# Sheet1.net
KiCad netlist of a schematic drawn in Altium Designer
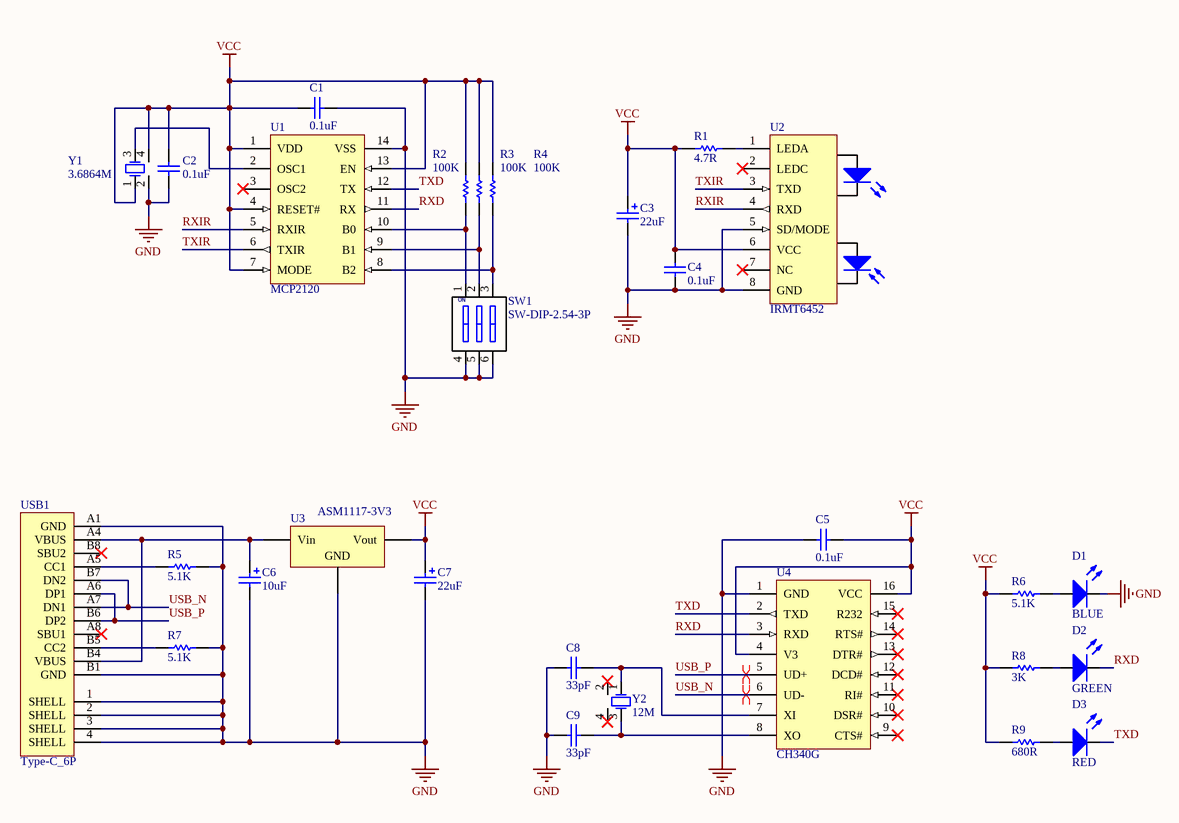
[diagram p0: Sheet1.SchDoc]

(export (version "E")
  (design (tool "Eeschema 10.0.6"))
  (components
    (comp (ref "C1")
      (value "0.1uF")
      (footprint "0603-CAP")
      (libsource (lib "izilzty_Library_Passive") (part "CAP-0603"))
    )
    (comp (ref "C2")
      (value "0.1uF")
      (footprint "0603-CAP")
      (libsource (lib "izilzty_Library_Passive") (part "CAP-0603"))
    )
    (comp (ref "C3")
      (value "22uF")
      (footprint "3216-TCAP_M")
      (libsource (lib "izilzty_Library_Passive") (part "CAP-T-3216"))
    )
    (comp (ref "C4")
      (value "0.1uF")
      (footprint "0603-CAP")
      (libsource (lib "izilzty_Library_Passive") (part "CAP-0603"))
    )
    (comp (ref "C5")
      (value "0.1uF")
      (footprint "0603-CAP")
      (libsource (lib "izilzty_Library_Passive") (part "CAP-0603"))
    )
    (comp (ref "C6")
      (value "10uF")
      (footprint "3216-TCAP_M")
      (libsource (lib "izilzty_Library_Passive") (part "CAP-T-3216"))
    )
    (comp (ref "C7")
      (value "22uF")
      (footprint "3216-TCAP_M")
      (libsource (lib "izilzty_Library_Passive") (part "CAP-T-3216"))
    )
    (comp (ref "C8")
      (value "33pF")
      (footprint "0603-CAP")
      (libsource (lib "izilzty_Library_Passive") (part "CAP-0603"))
    )
    (comp (ref "C9")
      (value "33pF")
      (footprint "0603-CAP")
      (libsource (lib "izilzty_Library_Passive") (part "CAP-0603"))
    )
    (comp (ref "D1")
      (value "BLUE")
      (footprint "0603-LED")
      (libsource (lib "izilzty_Library_Passive") (part "LED-0603"))
    )
    (comp (ref "D2")
      (value "GREEN")
      (footprint "0603-LED")
      (libsource (lib "izilzty_Library_Passive") (part "LED-0603"))
    )
    (comp (ref "D3")
      (value "RED")
      (footprint "0603-LED")
      (libsource (lib "izilzty_Library_Passive") (part "LED-0603"))
    )
    (comp (ref "R1")
      (value "4.7R")
      (footprint "0603-RES")
      (libsource (lib "izilzty_Library_Passive") (part "RES-0603"))
    )
    (comp (ref "R2")
      (value "100K")
      (footprint "0603-RES")
      (libsource (lib "izilzty_Library_Passive") (part "RES-0603"))
    )
    (comp (ref "R3")
      (value "100K")
      (footprint "0603-RES")
      (libsource (lib "izilzty_Library_Passive") (part "RES-0603"))
    )
    (comp (ref "R4")
      (value "100K")
      (footprint "0603-RES")
      (libsource (lib "izilzty_Library_Passive") (part "RES-0603"))
    )
    (comp (ref "R5")
      (value "5.1K")
      (footprint "0603-RES")
      (libsource (lib "izilzty_Library_Passive") (part "RES-0603"))
    )
    (comp (ref "R6")
      (value "5.1K")
      (footprint "0603-RES")
      (libsource (lib "izilzty_Library_Passive") (part "RES-0603"))
    )
    (comp (ref "R7")
      (value "5.1K")
      (footprint "0603-RES")
      (libsource (lib "izilzty_Library_Passive") (part "RES-0603"))
    )
    (comp (ref "R8")
      (value "3K")
      (footprint "0603-RES")
      (libsource (lib "izilzty_Library_Passive") (part "RES-0603"))
    )
    (comp (ref "R9")
      (value "680R")
      (footprint "0603-RES")
      (libsource (lib "izilzty_Library_Passive") (part "RES-0603"))
    )
    (comp (ref "SW1")
      (value "SW-DIP-2.54-3P")
      (footprint "SWITCH-DIP-2.54-3P")
      (libsource (lib "izilzty_Library_Passive") (part "SW-DIP-2.54-3P"))
    )
    (comp (ref "U1")
      (value "MCP2120")
      (footprint "SOP-14_M")
      (description "Infrared Encoder/Decoder")
      (libsource (lib "izilzty_Library_IC") (part "MCP2120"))
    )
    (comp (ref "U2")
      (value "IRMT6452")
      (footprint "IRMT6452_M")
      (description "4 Mb/s Infrared Data Transceiver")
      (libsource (lib "izilzty_Library_IC") (part "IRMT6452"))
    )
    (comp (ref "U3")
      (value "ASM1117-3V3")
      (footprint "SOT-89-3_M")
      (description "Voltage Regular (SOT-89)")
      (libsource (lib "izilzty_Library_IC") (part "VREG-SOT-89"))
    )
    (comp (ref "U4")
      (value "CH340G")
      (footprint "SOP-16_M")
      (description "USB转串口芯片")
      (libsource (lib "izilzty_Library_IC") (part "CH340G"))
    )
    (comp (ref "USB1")
      (value "Type-C_6P")
      (footprint "TYPE-C_16P")
      (libsource (lib "izilzty_Library_Connector") (part "Type-C_6P"))
    )
    (comp (ref "Y1")
      (value "3.6864M")
      (footprint "CRYSTAL_3225SMD_M")
      (description "oscillator")
      (libsource (lib "izilzty_Library_Passive") (part "XTAL-3225SMD"))
    )
    (comp (ref "Y2")
      (value "12M")
      (footprint "CRYSTAL_3225SMD_M")
      (description "crystal")
      (libsource (lib "izilzty_Library_Passive") (part "XTAL-3225SMD"))
    )
  )
  (nets
    (net (code "1") (name "/RXD") (class "Default")
      (node (ref "D2") (pin "1") (pinfunction "K_1") (pintype "passive"))
      (node (ref "U1") (pin "11") (pinfunction "RX_11") (pintype "output"))
      (node (ref "U4") (pin "3") (pinfunction "RXD_3") (pintype "input"))
    )
    (net (code "2") (name "/RXIR") (class "Default")
      (node (ref "U1") (pin "5") (pinfunction "RXIR_5") (pintype "input"))
      (node (ref "U2") (pin "4") (pinfunction "RXD_4") (pintype "output"))
    )
    (net (code "3") (name "/TXD") (class "Default")
      (node (ref "D3") (pin "1") (pinfunction "K_1") (pintype "passive"))
      (node (ref "U1") (pin "12") (pinfunction "TX_12") (pintype "input"))
      (node (ref "U4") (pin "2") (pinfunction "TXD_2") (pintype "output"))
    )
    (net (code "4") (name "/TXIR") (class "Default")
      (node (ref "U1") (pin "6") (pinfunction "TXIR_6") (pintype "output"))
      (node (ref "U2") (pin "3") (pinfunction "TXD_3") (pintype "input"))
    )
    (net (code "5") (name "/USB_N") (class "Default")
      (node (ref "U4") (pin "6") (pinfunction "UD-_6") (pintype "passive"))
      (node (ref "USB1") (pin "A7") (pinfunction "DN1_A7") (pintype "passive"))
      (node (ref "USB1") (pin "B7") (pinfunction "DN2_B7") (pintype "passive"))
    )
    (net (code "6") (name "/USB_P") (class "Default")
      (node (ref "U4") (pin "5") (pinfunction "UD+_5") (pintype "passive"))
      (node (ref "USB1") (pin "A6") (pinfunction "DP1_A6") (pintype "passive"))
      (node (ref "USB1") (pin "B6") (pinfunction "DP2_B6") (pintype "passive"))
    )
    (net (code "7") (name "GND") (class "Default")
      (node (ref "C1") (pin "2") (pinfunction "2_2") (pintype "passive"))
      (node (ref "C2") (pin "1") (pinfunction "1_1") (pintype "passive"))
      (node (ref "C3") (pin "2") (pinfunction "2_2") (pintype "passive"))
      (node (ref "C4") (pin "1") (pinfunction "1_1") (pintype "passive"))
      (node (ref "C5") (pin "1") (pinfunction "1_1") (pintype "passive"))
      (node (ref "C6") (pin "2") (pinfunction "2_2") (pintype "passive"))
      (node (ref "C7") (pin "2") (pinfunction "2_2") (pintype "passive"))
      (node (ref "C8") (pin "1") (pinfunction "1_1") (pintype "passive"))
      (node (ref "C9") (pin "2") (pinfunction "2_2") (pintype "passive"))
      (node (ref "D1") (pin "1") (pinfunction "K_1") (pintype "passive"))
      (node (ref "R5") (pin "1") (pinfunction "1_1") (pintype "passive"))
      (node (ref "R7") (pin "1") (pinfunction "1_1") (pintype "passive"))
      (node (ref "SW1") (pin "4") (pinfunction "B4_4") (pintype "passive"))
      (node (ref "SW1") (pin "5") (pinfunction "B5_5") (pintype "passive"))
      (node (ref "SW1") (pin "6") (pinfunction "B6_6") (pintype "passive"))
      (node (ref "U1") (pin "14") (pinfunction "VSS_14") (pintype "power_in"))
      (node (ref "U2") (pin "5") (pinfunction "SD/MODE_5") (pintype "input"))
      (node (ref "U2") (pin "8") (pinfunction "GND_8") (pintype "power_in"))
      (node (ref "U3") (pin "1") (pinfunction "GND_1") (pintype "passive"))
      (node (ref "U4") (pin "1") (pinfunction "GND_1") (pintype "power_in"))
      (node (ref "USB1") (pin "1") (pinfunction "SHELL_1") (pintype "passive"))
      (node (ref "USB1") (pin "2") (pinfunction "SHELL_2") (pintype "passive"))
      (node (ref "USB1") (pin "3") (pinfunction "SHELL_3") (pintype "passive"))
      (node (ref "USB1") (pin "4") (pinfunction "SHELL_4") (pintype "passive"))
      (node (ref "USB1") (pin "A1") (pinfunction "GND_A1") (pintype "passive"))
      (node (ref "USB1") (pin "B1") (pinfunction "GND_B1") (pintype "passive"))
      (node (ref "Y1") (pin "2") (pinfunction "GND_2") (pintype "passive"))
    )
    (net (code "8") (name "Net-(D1-A)") (class "Default")
      (node (ref "D1") (pin "2") (pinfunction "A_2") (pintype "passive"))
      (node (ref "R6") (pin "2") (pinfunction "2_2") (pintype "passive"))
    )
    (net (code "9") (name "Net-(D2-A)") (class "Default")
      (node (ref "D2") (pin "2") (pinfunction "A_2") (pintype "passive"))
      (node (ref "R8") (pin "2") (pinfunction "2_2") (pintype "passive"))
    )
    (net (code "10") (name "Net-(D3-A)") (class "Default")
      (node (ref "D3") (pin "2") (pinfunction "A_2") (pintype "passive"))
      (node (ref "R9") (pin "2") (pinfunction "2_2") (pintype "passive"))
    )
    (net (code "11") (name "Net-(SW1-A1)") (class "Default")
      (node (ref "R2") (pin "1") (pinfunction "1_1") (pintype "passive"))
      (node (ref "SW1") (pin "1") (pinfunction "A1_1") (pintype "passive"))
      (node (ref "U1") (pin "10") (pinfunction "B0_10") (pintype "input"))
    )
    (net (code "12") (name "Net-(SW1-A2)") (class "Default")
      (node (ref "R3") (pin "1") (pinfunction "1_1") (pintype "passive"))
      (node (ref "SW1") (pin "2") (pinfunction "A2_2") (pintype "passive"))
      (node (ref "U1") (pin "9") (pinfunction "B1_9") (pintype "input"))
    )
    (net (code "13") (name "Net-(SW1-A3)") (class "Default")
      (node (ref "R4") (pin "1") (pinfunction "1_1") (pintype "passive"))
      (node (ref "SW1") (pin "3") (pinfunction "A3_3") (pintype "passive"))
      (node (ref "U1") (pin "8") (pinfunction "B2_8") (pintype "input"))
    )
    (net (code "14") (name "Net-(U1-OSC1)") (class "Default")
      (node (ref "U1") (pin "2") (pinfunction "OSC1_2") (pintype "passive"))
      (node (ref "Y1") (pin "3") (pinfunction "OSC2_3") (pintype "passive"))
    )
    (net (code "15") (name "Net-(U2-LEDA)") (class "Default")
      (node (ref "R1") (pin "2") (pinfunction "2_2") (pintype "passive"))
      (node (ref "U2") (pin "1") (pinfunction "LEDA_1") (pintype "passive"))
    )
    (net (code "16") (name "Net-(U3-Vin)") (class "Default")
      (node (ref "C6") (pin "1") (pinfunction "1_1") (pintype "passive"))
      (node (ref "U3") (pin "3") (pinfunction "Vin_3") (pintype "passive"))
      (node (ref "USB1") (pin "A4") (pinfunction "VBUS_A4") (pintype "passive"))
      (node (ref "USB1") (pin "B4") (pinfunction "VBUS_B4") (pintype "passive"))
    )
    (net (code "17") (name "Net-(U4-XI)") (class "Default")
      (node (ref "C8") (pin "2") (pinfunction "2_2") (pintype "passive"))
      (node (ref "U4") (pin "7") (pinfunction "XI_7") (pintype "passive"))
      (node (ref "Y2") (pin "1") (pinfunction "OSC1_1") (pintype "passive"))
    )
    (net (code "18") (name "Net-(U4-XO)") (class "Default")
      (node (ref "C9") (pin "1") (pinfunction "1_1") (pintype "passive"))
      (node (ref "U4") (pin "8") (pinfunction "XO_8") (pintype "passive"))
      (node (ref "Y2") (pin "3") (pinfunction "OSC2_3") (pintype "passive"))
    )
    (net (code "19") (name "Net-(USB1-CC1)") (class "Default")
      (node (ref "R5") (pin "2") (pinfunction "2_2") (pintype "passive"))
      (node (ref "USB1") (pin "A5") (pinfunction "CC1_A5") (pintype "passive"))
    )
    (net (code "20") (name "Net-(USB1-CC2)") (class "Default")
      (node (ref "R7") (pin "2") (pinfunction "2_2") (pintype "passive"))
      (node (ref "USB1") (pin "B5") (pinfunction "CC2_B5") (pintype "passive"))
    )
    (net (code "21") (name "VCC") (class "Default")
      (node (ref "C1") (pin "1") (pinfunction "1_1") (pintype "passive"))
      (node (ref "C2") (pin "2") (pinfunction "2_2") (pintype "passive"))
      (node (ref "C3") (pin "1") (pinfunction "1_1") (pintype "passive"))
      (node (ref "C4") (pin "2") (pinfunction "2_2") (pintype "passive"))
      (node (ref "C5") (pin "2") (pinfunction "2_2") (pintype "passive"))
      (node (ref "C7") (pin "1") (pinfunction "1_1") (pintype "passive"))
      (node (ref "R1") (pin "1") (pinfunction "1_1") (pintype "passive"))
      (node (ref "R2") (pin "2") (pinfunction "2_2") (pintype "passive"))
      (node (ref "R3") (pin "2") (pinfunction "2_2") (pintype "passive"))
      (node (ref "R4") (pin "2") (pinfunction "2_2") (pintype "passive"))
      (node (ref "R6") (pin "1") (pinfunction "1_1") (pintype "passive"))
      (node (ref "R8") (pin "1") (pinfunction "1_1") (pintype "passive"))
      (node (ref "R9") (pin "1") (pinfunction "1_1") (pintype "passive"))
      (node (ref "U1") (pin "1") (pinfunction "VDD_1") (pintype "power_in"))
      (node (ref "U1") (pin "13") (pinfunction "EN_13") (pintype "input"))
      (node (ref "U1") (pin "4") (pinfunction "RESET#_4") (pintype "input"))
      (node (ref "U1") (pin "7") (pinfunction "MODE_7") (pintype "input"))
      (node (ref "U2") (pin "6") (pinfunction "VCC_6") (pintype "power_in"))
      (node (ref "U3") (pin "2") (pinfunction "Vout_2") (pintype "passive"))
      (node (ref "U4") (pin "16") (pinfunction "VCC_16") (pintype "power_in"))
      (node (ref "U4") (pin "4") (pinfunction "V3_4") (pintype "power_in"))
      (node (ref "Y1") (pin "1") (pinfunction "OSC1_1") (pintype "passive"))
      (node (ref "Y1") (pin "4") (pinfunction "GND_4") (pintype "passive"))
    )
    (net (code "22") (name "unconnected-(U1-OSC2-Pad3)") (class "Default")
      (node (ref "U1") (pin "3") (pinfunction "OSC2_3") (pintype "passive+no_connect"))
    )
    (net (code "23") (name "unconnected-(U2-LEDC-Pad2)") (class "Default")
      (node (ref "U2") (pin "2") (pinfunction "LEDC_2") (pintype "passive+no_connect"))
    )
    (net (code "24") (name "unconnected-(U2-NC-Pad7)") (class "Default")
      (node (ref "U2") (pin "7") (pinfunction "NC_7") (pintype "passive+no_connect"))
    )
    (net (code "25") (name "unconnected-(U4-CTS#-Pad9)") (class "Default")
      (node (ref "U4") (pin "9") (pinfunction "CTS#_9") (pintype "input+no_connect"))
    )
    (net (code "26") (name "unconnected-(U4-DCD#-Pad12)") (class "Default")
      (node (ref "U4") (pin "12") (pinfunction "DCD#_12") (pintype "input+no_connect"))
    )
    (net (code "27") (name "unconnected-(U4-DSR#-Pad10)") (class "Default")
      (node (ref "U4") (pin "10") (pinfunction "DSR#_10") (pintype "input+no_connect"))
    )
    (net (code "28") (name "unconnected-(U4-DTR#-Pad13)") (class "Default")
      (node (ref "U4") (pin "13") (pinfunction "DTR#_13") (pintype "output+no_connect"))
    )
    (net (code "29") (name "unconnected-(U4-R232-Pad15)") (class "Default")
      (node (ref "U4") (pin "15") (pinfunction "R232_15") (pintype "input+no_connect"))
    )
    (net (code "30") (name "unconnected-(U4-RI#-Pad11)") (class "Default")
      (node (ref "U4") (pin "11") (pinfunction "RI#_11") (pintype "input+no_connect"))
    )
    (net (code "31") (name "unconnected-(U4-RTS#-Pad14)") (class "Default")
      (node (ref "U4") (pin "14") (pinfunction "RTS#_14") (pintype "output+no_connect"))
    )
    (net (code "32") (name "unconnected-(USB1-SBU1-PadA8)") (class "Default")
      (node (ref "USB1") (pin "A8") (pinfunction "SBU1_A8") (pintype "passive+no_connect"))
    )
    (net (code "33") (name "unconnected-(USB1-SBU2-PadB8)") (class "Default")
      (node (ref "USB1") (pin "B8") (pinfunction "SBU2_B8") (pintype "passive+no_connect"))
    )
    (net (code "34") (name "unconnected-(Y2-GND-Pad2)") (class "Default")
      (node (ref "Y2") (pin "2") (pinfunction "GND_2") (pintype "passive+no_connect"))
    )
    (net (code "35") (name "unconnected-(Y2-GND-Pad4)") (class "Default")
      (node (ref "Y2") (pin "4") (pinfunction "GND_4") (pintype "passive+no_connect"))
    )
  )
)
